# portable-atmega328.net
KiCad netlist of a schematic drawn in EAGLE
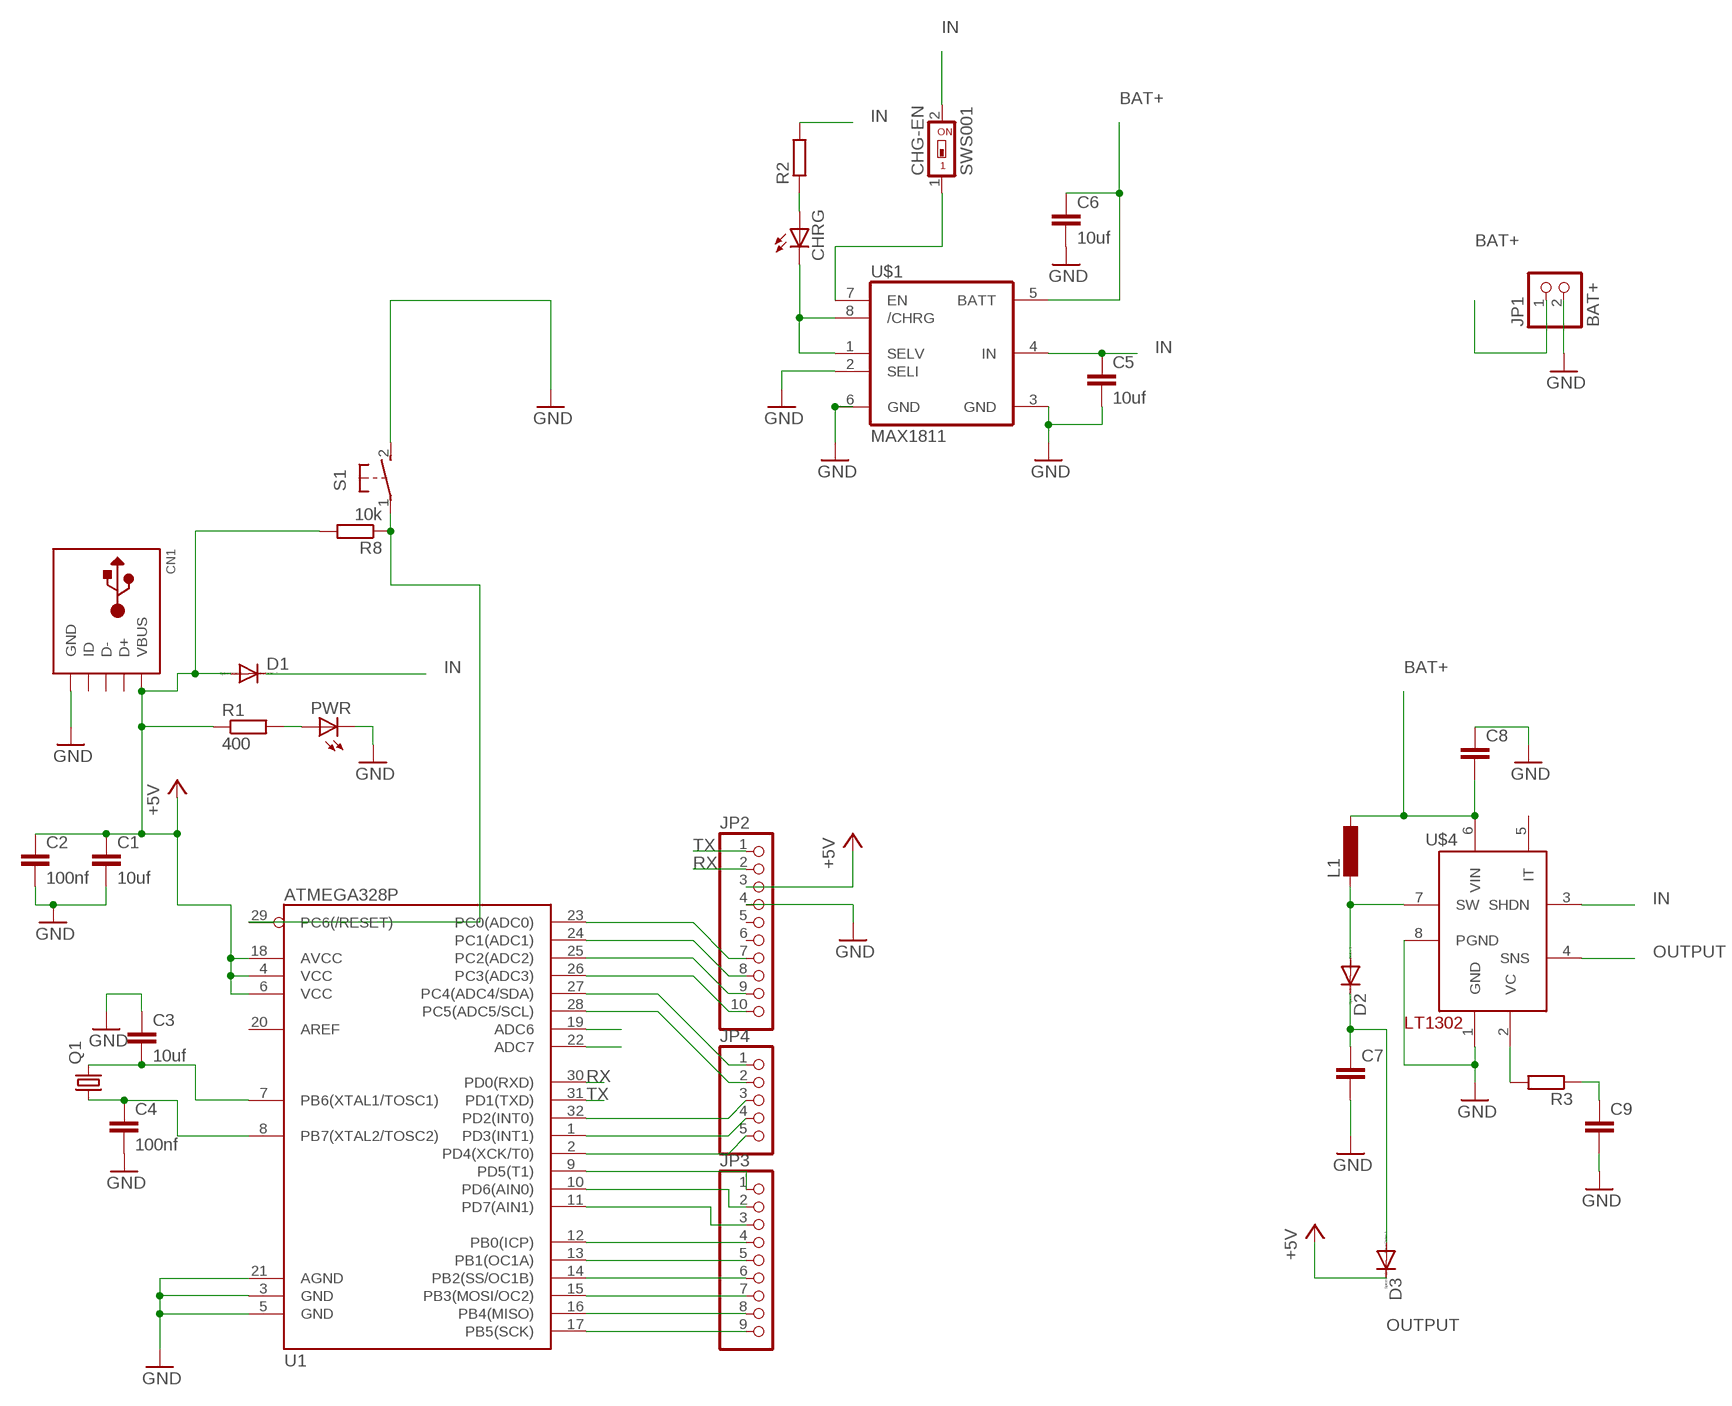
[diagram p0: schematic, sheet 1]

(export (version "E")
  (design (tool "Eeschema 10.0.6"))
  (components
    (comp (ref "C1")
      (value "10uf")
      (footprint "eagle-import:C1206")
      (libsource (lib "eagle-import") (part "C-EUC1206"))
    )
    (comp (ref "C2")
      (value "100nf")
      (footprint "eagle-import:C1206")
      (libsource (lib "eagle-import") (part "C-EUC1206"))
    )
    (comp (ref "C3")
      (value "10uf")
      (footprint "eagle-import:C1206")
      (libsource (lib "eagle-import") (part "C-EUC1206"))
    )
    (comp (ref "C4")
      (value "100nf")
      (footprint "eagle-import:C1206")
      (libsource (lib "eagle-import") (part "C-EUC1206"))
    )
    (comp (ref "C5")
      (value "10uf")
      (footprint "eagle-import:C1206")
      (libsource (lib "eagle-import") (part "C-EUC1206"))
    )
    (comp (ref "C6")
      (value "10uf")
      (footprint "eagle-import:C1206")
      (libsource (lib "eagle-import") (part "C-EUC1206"))
    )
    (comp (ref "C7")
      (value "C-EUC3225")
      (footprint "eagle-import:C3225")
      (libsource (lib "eagle-import") (part "C-EUC3225"))
    )
    (comp (ref "C8")
      (value "C-EUC1206")
      (footprint "eagle-import:C1206")
      (libsource (lib "eagle-import") (part "C-EUC1206"))
    )
    (comp (ref "C9")
      (value "C-EUC1206")
      (footprint "eagle-import:C1206")
      (libsource (lib "eagle-import") (part "C-EUC1206"))
    )
    (comp (ref "CHG-EN")
      (value "SWS001")
      (footprint "eagle-import:SMS-001")
      (libsource (lib "eagle-import") (part "SWS001"))
    )
    (comp (ref "CHRG")
      (value "LEDCHIPLED_1206")
      (footprint "eagle-import:CHIPLED_1206")
      (libsource (lib "eagle-import") (part "LEDCHIPLED_1206"))
    )
    (comp (ref "CN1")
      (value "USBMINIB")
      (footprint "eagle-import:USB-MINIB")
      (libsource (lib "eagle-import") (part "USBMINIB"))
    )
    (comp (ref "D1")
      (value "DIODE-DO214AA")
      (footprint "eagle-import:DO214AA")
      (libsource (lib "eagle-import") (part "DIODE-DO214AA"))
    )
    (comp (ref "D2")
      (value "DIODE-DO214AA")
      (footprint "eagle-import:DO214AA")
      (libsource (lib "eagle-import") (part "DIODE-DO214AA"))
    )
    (comp (ref "D3")
      (value "DIODE-DO214AA")
      (footprint "eagle-import:DO214AA")
      (libsource (lib "eagle-import") (part "DIODE-DO214AA"))
    )
    (comp (ref "JP1")
      (value "BAT+")
      (footprint "eagle-import:1X02")
      (libsource (lib "eagle-import") (part "PINHD-1X2"))
    )
    (comp (ref "JP2")
      (value "PINHD-1X10")
      (footprint "eagle-import:1X10")
      (libsource (lib "eagle-import") (part "PINHD-1X10"))
    )
    (comp (ref "JP3")
      (value "PINHD-1X9")
      (footprint "eagle-import:1X09")
      (libsource (lib "eagle-import") (part "PINHD-1X9"))
    )
    (comp (ref "JP4")
      (value "PINHD-1X5")
      (footprint "eagle-import:1X05")
      (libsource (lib "eagle-import") (part "PINHD-1X5"))
    )
    (comp (ref "L1")
      (value "DO3316P")
      (footprint "eagle-import:DO3316P")
      (libsource (lib "eagle-import") (part "DO3316P"))
    )
    (comp (ref "PWR")
      (value "LEDCHIPLED_1206")
      (footprint "eagle-import:CHIPLED_1206")
      (libsource (lib "eagle-import") (part "LEDCHIPLED_1206"))
    )
    (comp (ref "Q1")
      (value "CRYSTALHC49S")
      (footprint "eagle-import:HC49_S")
      (libsource (lib "eagle-import") (part "CRYSTALHC49S"))
    )
    (comp (ref "R1")
      (value "400")
      (footprint "eagle-import:R1206")
      (libsource (lib "eagle-import") (part "R-EU_R1206"))
    )
    (comp (ref "R2")
      (value "R-EU_R1206")
      (footprint "eagle-import:R1206")
      (libsource (lib "eagle-import") (part "R-EU_R1206"))
    )
    (comp (ref "R3")
      (value "R-EU_R1206")
      (footprint "eagle-import:R1206")
      (libsource (lib "eagle-import") (part "R-EU_R1206"))
    )
    (comp (ref "R8")
      (value "10k")
      (footprint "eagle-import:R0805")
      (libsource (lib "eagle-import") (part "solar3-1_R-EU_R0805"))
    )
    (comp (ref "S1")
      (value "31-XXSKINNY")
      (footprint "eagle-import:B3F-31XX-SKINNIER")
      (libsource (lib "eagle-import") (part "31-XXSKINNY"))
    )
    (comp (ref "U$1")
      (value "MAX1811")
      (footprint "eagle-import:SO08")
      (libsource (lib "eagle-import") (part "MAX1811"))
    )
    (comp (ref "U$4")
      (value "LT1302SO8")
      (footprint "eagle-import:SO08")
      (libsource (lib "eagle-import") (part "LT1302SO8"))
    )
    (comp (ref "U1")
      (value "ATMEGA328P")
      (footprint "eagle-import:TQFP32-08")
      (libsource (lib "eagle-import") (part "ATMEGA328_SMT"))
    )
  )
  (nets
    (net (code "1") (name "+5V") (class "Default")
      (node (ref "C1") (pin "1") (pinfunction "1_1") (pintype "passive"))
      (node (ref "C2") (pin "1") (pinfunction "1_1") (pintype "passive"))
      (node (ref "CN1") (pin "VBUS") (pinfunction "VBUS_VBUS") (pintype "power_in"))
      (node (ref "D1") (pin "A") (pinfunction "A_A") (pintype "passive"))
      (node (ref "D3") (pin "C") (pinfunction "C_C") (pintype "passive"))
      (node (ref "JP2") (pin "3") (pinfunction "3_3") (pintype "passive"))
      (node (ref "R1") (pin "1") (pinfunction "1_1") (pintype "passive"))
      (node (ref "R8") (pin "2") (pinfunction "2_2") (pintype "passive"))
      (node (ref "U1") (pin "18") (pinfunction "AVCC_18") (pintype "bidirectional"))
      (node (ref "U1") (pin "4") (pinfunction "VCC_4") (pintype "bidirectional"))
      (node (ref "U1") (pin "6") (pinfunction "VCC_6") (pintype "bidirectional"))
    )
    (net (code "2") (name "/BAT+") (class "Default")
      (node (ref "C6") (pin "1") (pinfunction "1_1") (pintype "passive"))
      (node (ref "C8") (pin "2") (pinfunction "2_2") (pintype "passive"))
      (node (ref "JP1") (pin "1") (pinfunction "1_1") (pintype "passive"))
      (node (ref "L1") (pin "2") (pinfunction "2_2") (pintype "passive"))
      (node (ref "U$1") (pin "5") (pinfunction "BATT_5") (pintype "output"))
      (node (ref "U$4") (pin "6") (pinfunction "VIN_6") (pintype "input"))
    )
    (net (code "3") (name "/IN") (class "Default")
      (node (ref "C5") (pin "1") (pinfunction "1_1") (pintype "passive"))
      (node (ref "CHG-EN") (pin "2") (pinfunction "2_2") (pintype "passive"))
      (node (ref "D1") (pin "C") (pinfunction "C_C") (pintype "passive"))
      (node (ref "R2") (pin "2") (pinfunction "2_2") (pintype "passive"))
      (node (ref "U$1") (pin "4") (pinfunction "IN_4") (pintype "power_in"))
      (node (ref "U$4") (pin "3") (pinfunction "SHDN_3") (pintype "input"))
    )
    (net (code "4") (name "/OUTPUT") (class "Default")
      (node (ref "C7") (pin "1") (pinfunction "1_1") (pintype "passive"))
      (node (ref "D2") (pin "C") (pinfunction "C_C") (pintype "passive"))
      (node (ref "D3") (pin "A") (pinfunction "A_A") (pintype "passive"))
      (node (ref "U$4") (pin "4") (pinfunction "SNS_4") (pintype "passive"))
    )
    (net (code "5") (name "/RX") (class "Default")
      (node (ref "JP2") (pin "2") (pinfunction "2_2") (pintype "passive"))
      (node (ref "U1") (pin "30") (pinfunction "PD0(RXD)_30") (pintype "bidirectional"))
    )
    (net (code "6") (name "/TX") (class "Default")
      (node (ref "JP2") (pin "1") (pinfunction "1_1") (pintype "passive"))
      (node (ref "U1") (pin "31") (pinfunction "PD1(TXD)_31") (pintype "bidirectional"))
    )
    (net (code "7") (name "GND") (class "Default")
      (node (ref "C1") (pin "2") (pinfunction "2_2") (pintype "passive"))
      (node (ref "C2") (pin "2") (pinfunction "2_2") (pintype "passive"))
      (node (ref "C3") (pin "1") (pinfunction "1_1") (pintype "passive"))
      (node (ref "C4") (pin "2") (pinfunction "2_2") (pintype "passive"))
      (node (ref "C5") (pin "2") (pinfunction "2_2") (pintype "passive"))
      (node (ref "C6") (pin "2") (pinfunction "2_2") (pintype "passive"))
      (node (ref "C7") (pin "2") (pinfunction "2_2") (pintype "passive"))
      (node (ref "C8") (pin "1") (pinfunction "1_1") (pintype "passive"))
      (node (ref "C9") (pin "2") (pinfunction "2_2") (pintype "passive"))
      (node (ref "CN1") (pin "GND") (pinfunction "GND_GND") (pintype "power_in"))
      (node (ref "JP1") (pin "2") (pinfunction "2_2") (pintype "passive"))
      (node (ref "JP2") (pin "4") (pinfunction "4_4") (pintype "passive"))
      (node (ref "PWR") (pin "C") (pinfunction "C_C") (pintype "passive"))
      (node (ref "S1") (pin "2") (pinfunction "S_2") (pintype "passive"))
      (node (ref "U$1") (pin "2") (pinfunction "SELI_2") (pintype "input"))
      (node (ref "U$1") (pin "3") (pinfunction "GND_3") (pintype "power_in"))
      (node (ref "U$1") (pin "6") (pinfunction "GND_6") (pintype "power_in"))
      (node (ref "U$4") (pin "1") (pinfunction "GND_1") (pintype "input"))
      (node (ref "U$4") (pin "8") (pinfunction "PGND_8") (pintype "input"))
      (node (ref "U1") (pin "21") (pinfunction "AGND_21") (pintype "bidirectional"))
      (node (ref "U1") (pin "3") (pinfunction "GND_3") (pintype "bidirectional"))
      (node (ref "U1") (pin "5") (pinfunction "GND_5") (pintype "bidirectional"))
    )
    (net (code "8") (name "Net-(C9-Pad1)") (class "Default")
      (node (ref "C9") (pin "1") (pinfunction "1_1") (pintype "passive"))
      (node (ref "R3") (pin "1") (pinfunction "1_1") (pintype "passive"))
    )
    (net (code "9") (name "Net-(CHRG-PadA)") (class "Default")
      (node (ref "CHRG") (pin "A") (pinfunction "A_A") (pintype "passive"))
      (node (ref "R2") (pin "1") (pinfunction "1_1") (pintype "passive"))
    )
    (net (code "10") (name "Net-(PWR-PadA)") (class "Default")
      (node (ref "PWR") (pin "A") (pinfunction "A_A") (pintype "passive"))
      (node (ref "R1") (pin "2") (pinfunction "2_2") (pintype "passive"))
    )
    (net (code "11") (name "Net-(S1-P)") (class "Default")
      (node (ref "R8") (pin "1") (pinfunction "1_1") (pintype "passive"))
      (node (ref "S1") (pin "1") (pinfunction "P_1") (pintype "passive"))
      (node (ref "U1") (pin "29") (pinfunction "PC6(/RESET)_29") (pintype "bidirectional"))
    )
    (net (code "12") (name "Net-(U$1-EN)") (class "Default")
      (node (ref "CHG-EN") (pin "1") (pinfunction "1_1") (pintype "passive"))
      (node (ref "U$1") (pin "7") (pinfunction "EN_7") (pintype "input"))
    )
    (net (code "13") (name "Net-(U$1-SELV)") (class "Default")
      (node (ref "CHRG") (pin "C") (pinfunction "C_C") (pintype "passive"))
      (node (ref "U$1") (pin "1") (pinfunction "SELV_1") (pintype "input"))
      (node (ref "U$1") (pin "8") (pinfunction "/CHRG_8") (pintype "output"))
    )
    (net (code "14") (name "Net-(U$4-SW)") (class "Default")
      (node (ref "D2") (pin "A") (pinfunction "A_A") (pintype "passive"))
      (node (ref "L1") (pin "1") (pinfunction "1_1") (pintype "passive"))
      (node (ref "U$4") (pin "7") (pinfunction "SW_7") (pintype "input"))
    )
    (net (code "15") (name "Net-(U$4-VC)") (class "Default")
      (node (ref "R3") (pin "2") (pinfunction "2_2") (pintype "passive"))
      (node (ref "U$4") (pin "2") (pinfunction "VC_2") (pintype "passive"))
    )
    (net (code "16") (name "Net-(U1-PB0(ICP))") (class "Default")
      (node (ref "JP3") (pin "4") (pinfunction "4_4") (pintype "passive"))
      (node (ref "U1") (pin "12") (pinfunction "PB0(ICP)_12") (pintype "bidirectional"))
    )
    (net (code "17") (name "Net-(U1-PB1(OC1A))") (class "Default")
      (node (ref "JP3") (pin "5") (pinfunction "5_5") (pintype "passive"))
      (node (ref "U1") (pin "13") (pinfunction "PB1(OC1A)_13") (pintype "bidirectional"))
    )
    (net (code "18") (name "Net-(U1-PB2(SS{slash}OC1B))") (class "Default")
      (node (ref "JP3") (pin "6") (pinfunction "6_6") (pintype "passive"))
      (node (ref "U1") (pin "14") (pinfunction "PB2(SS/OC1B)_14") (pintype "bidirectional"))
    )
    (net (code "19") (name "Net-(U1-PB3(MOSI{slash}OC2))") (class "Default")
      (node (ref "JP3") (pin "7") (pinfunction "7_7") (pintype "passive"))
      (node (ref "U1") (pin "15") (pinfunction "PB3(MOSI/OC2)_15") (pintype "bidirectional"))
    )
    (net (code "20") (name "Net-(U1-PB4(MISO))") (class "Default")
      (node (ref "JP3") (pin "8") (pinfunction "8_8") (pintype "passive"))
      (node (ref "U1") (pin "16") (pinfunction "PB4(MISO)_16") (pintype "bidirectional"))
    )
    (net (code "21") (name "Net-(U1-PB5(SCK))") (class "Default")
      (node (ref "JP3") (pin "9") (pinfunction "9_9") (pintype "passive"))
      (node (ref "U1") (pin "17") (pinfunction "PB5(SCK)_17") (pintype "bidirectional"))
    )
    (net (code "22") (name "Net-(U1-PB6(XTAL1{slash}TOSC1))") (class "Default")
      (node (ref "C3") (pin "2") (pinfunction "2_2") (pintype "passive"))
      (node (ref "Q1") (pin "2") (pinfunction "2_2") (pintype "passive"))
      (node (ref "U1") (pin "7") (pinfunction "PB6(XTAL1/TOSC1)_7") (pintype "bidirectional"))
    )
    (net (code "23") (name "Net-(U1-PB7(XTAL2{slash}TOSC2))") (class "Default")
      (node (ref "C4") (pin "1") (pinfunction "1_1") (pintype "passive"))
      (node (ref "Q1") (pin "1") (pinfunction "1_1") (pintype "passive"))
      (node (ref "U1") (pin "8") (pinfunction "PB7(XTAL2/TOSC2)_8") (pintype "bidirectional"))
    )
    (net (code "24") (name "Net-(U1-PC0(ADC0))") (class "Default")
      (node (ref "JP2") (pin "7") (pinfunction "7_7") (pintype "passive"))
      (node (ref "U1") (pin "23") (pinfunction "PC0(ADC0)_23") (pintype "bidirectional"))
    )
    (net (code "25") (name "Net-(U1-PC1(ADC1))") (class "Default")
      (node (ref "JP2") (pin "8") (pinfunction "8_8") (pintype "passive"))
      (node (ref "U1") (pin "24") (pinfunction "PC1(ADC1)_24") (pintype "bidirectional"))
    )
    (net (code "26") (name "Net-(U1-PC2(ADC2))") (class "Default")
      (node (ref "JP2") (pin "9") (pinfunction "9_9") (pintype "passive"))
      (node (ref "U1") (pin "25") (pinfunction "PC2(ADC2)_25") (pintype "bidirectional"))
    )
    (net (code "27") (name "Net-(U1-PC3(ADC3))") (class "Default")
      (node (ref "JP2") (pin "10") (pinfunction "10_10") (pintype "passive"))
      (node (ref "U1") (pin "26") (pinfunction "PC3(ADC3)_26") (pintype "bidirectional"))
    )
    (net (code "28") (name "Net-(U1-PC4(ADC4{slash}SDA))") (class "Default")
      (node (ref "JP4") (pin "1") (pinfunction "1_1") (pintype "passive"))
      (node (ref "U1") (pin "27") (pinfunction "PC4(ADC4/SDA)_27") (pintype "bidirectional"))
    )
    (net (code "29") (name "Net-(U1-PC5(ADC5{slash}SCL))") (class "Default")
      (node (ref "JP4") (pin "2") (pinfunction "2_2") (pintype "passive"))
      (node (ref "U1") (pin "28") (pinfunction "PC5(ADC5/SCL)_28") (pintype "bidirectional"))
    )
    (net (code "30") (name "Net-(U1-PD2(INT0))") (class "Default")
      (node (ref "JP4") (pin "3") (pinfunction "3_3") (pintype "passive"))
      (node (ref "U1") (pin "32") (pinfunction "PD2(INT0)_32") (pintype "bidirectional"))
    )
    (net (code "31") (name "Net-(U1-PD3(INT1))") (class "Default")
      (node (ref "JP4") (pin "4") (pinfunction "4_4") (pintype "passive"))
      (node (ref "U1") (pin "1") (pinfunction "PD3(INT1)_1") (pintype "bidirectional"))
    )
    (net (code "32") (name "Net-(U1-PD4(XCK{slash}T0))") (class "Default")
      (node (ref "JP4") (pin "5") (pinfunction "5_5") (pintype "passive"))
      (node (ref "U1") (pin "2") (pinfunction "PD4(XCK/T0)_2") (pintype "bidirectional"))
    )
    (net (code "33") (name "Net-(U1-PD5(T1))") (class "Default")
      (node (ref "JP3") (pin "1") (pinfunction "1_1") (pintype "passive"))
      (node (ref "U1") (pin "9") (pinfunction "PD5(T1)_9") (pintype "bidirectional"))
    )
    (net (code "34") (name "Net-(U1-PD6(AIN0))") (class "Default")
      (node (ref "JP3") (pin "2") (pinfunction "2_2") (pintype "passive"))
      (node (ref "U1") (pin "10") (pinfunction "PD6(AIN0)_10") (pintype "bidirectional"))
    )
    (net (code "35") (name "Net-(U1-PD7(AIN1))") (class "Default")
      (node (ref "JP3") (pin "3") (pinfunction "3_3") (pintype "passive"))
      (node (ref "U1") (pin "11") (pinfunction "PD7(AIN1)_11") (pintype "bidirectional"))
    )
    (net (code "36") (name "unconnected-(CN1-PadD+)") (class "Default")
      (node (ref "CN1") (pin "D+") (pinfunction "D+_D+") (pintype "bidirectional"))
    )
    (net (code "37") (name "unconnected-(CN1-PadD-)") (class "Default")
      (node (ref "CN1") (pin "D-") (pinfunction "D-_D-") (pintype "bidirectional"))
    )
    (net (code "38") (name "unconnected-(CN1-PadID)") (class "Default")
      (node (ref "CN1") (pin "ID") (pinfunction "ID_ID") (pintype "bidirectional"))
    )
    (net (code "39") (name "unconnected-(JP2-Pad5)") (class "Default")
      (node (ref "JP2") (pin "5") (pinfunction "5_5") (pintype "passive"))
    )
    (net (code "40") (name "unconnected-(JP2-Pad6)") (class "Default")
      (node (ref "JP2") (pin "6") (pinfunction "6_6") (pintype "passive"))
    )
    (net (code "41") (name "unconnected-(U$4-IT-Pad5)") (class "Default")
      (node (ref "U$4") (pin "5") (pinfunction "IT_5") (pintype "input"))
    )
    (net (code "42") (name "unconnected-(U1-ADC6-Pad19)") (class "Default")
      (node (ref "U1") (pin "19") (pinfunction "ADC6_19") (pintype "bidirectional"))
    )
    (net (code "43") (name "unconnected-(U1-ADC7-Pad22)") (class "Default")
      (node (ref "U1") (pin "22") (pinfunction "ADC7_22") (pintype "bidirectional"))
    )
    (net (code "44") (name "unconnected-(U1-AREF-Pad20)") (class "Default")
      (node (ref "U1") (pin "20") (pinfunction "AREF_20") (pintype "bidirectional"))
    )
  )
)
